# voltmeter.net
KiCad netlist of a schematic drawn in Altium Designer
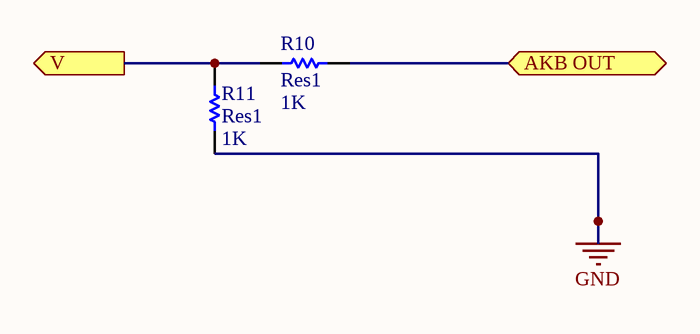
[diagram p0: voltmeter.SchDoc]

(export (version "E")
  (design (tool "Eeschema 10.0.6"))
  (components
    (comp (ref "R10")
      (value "Res1")
      (footprint "AXIAL-0.3")
      (description "Resistor")
      (fields (field (name "ALTIUM_VALUE") "1K") (field (name "PUBLISHER") "Altium Limited"))
      (libsource (lib "Miscellaneous Devices") (part "Res1"))
    )
    (comp (ref "R11")
      (value "Res1")
      (footprint "AXIAL-0.3")
      (description "Resistor")
      (fields (field (name "ALTIUM_VALUE") "1K") (field (name "PUBLISHER") "Altium Limited"))
      (libsource (lib "Miscellaneous Devices") (part "Res1"))
    )
  )
  (nets
    (net (code "1") (name "/AKB OUT") (class "Default")
      (node (ref "R10") (pin "2") (pinfunction "2_2") (pintype "passive"))
    )
    (net (code "2") (name "/V") (class "Default")
      (node (ref "R10") (pin "1") (pinfunction "1_1") (pintype "passive"))
      (node (ref "R11") (pin "2") (pinfunction "2_2") (pintype "passive"))
    )
    (net (code "3") (name "GND") (class "Default")
      (node (ref "R11") (pin "1") (pinfunction "1_1") (pintype "passive"))
    )
  )
)
